# Power.net
KiCad netlist of a schematic drawn in Altium Designer
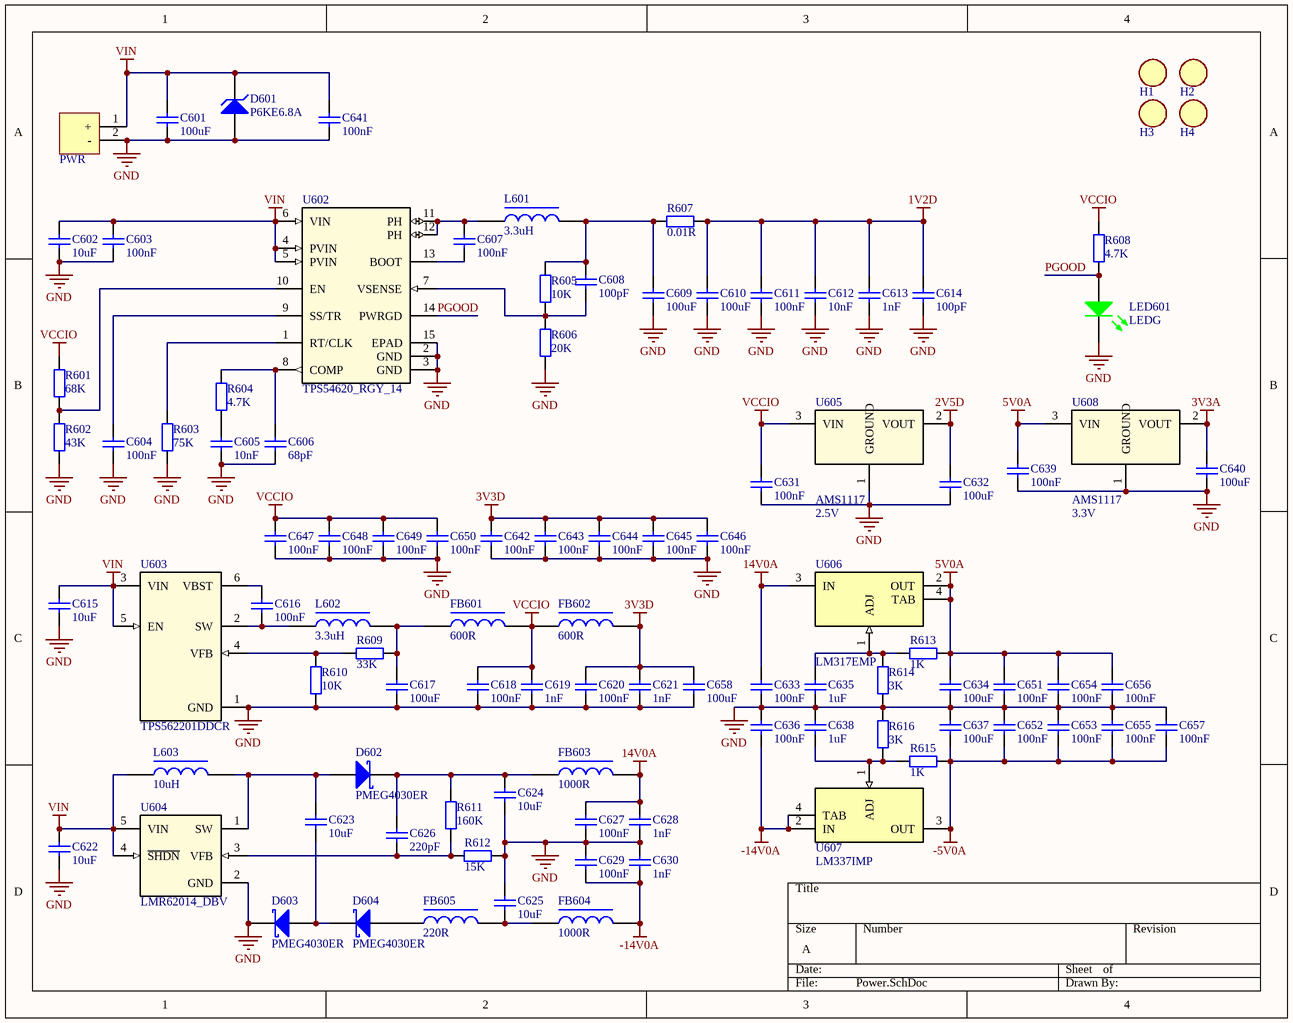
[diagram p0: Power.SchDoc]

(export (version "E")
  (design (tool "Eeschema 10.0.6"))
  (components
    (comp (ref "C601")
      (value "100uF")
      (footprint "1210C")
      (description "MLCC")
      (libsource (lib "Misc") (part "MLCC"))
    )
    (comp (ref "C602")
      (value "10uF")
      (footprint "1206C")
      (description "MLCC")
      (libsource (lib "Misc") (part "MLCC"))
    )
    (comp (ref "C603")
      (value "100nF")
      (footprint "0603C")
      (description "MLCC")
      (libsource (lib "Misc") (part "MLCC"))
    )
    (comp (ref "C604")
      (value "100nF")
      (footprint "0603C")
      (description "MLCC")
      (libsource (lib "Misc") (part "MLCC"))
    )
    (comp (ref "C605")
      (value "10nF")
      (footprint "0603C")
      (description "MLCC")
      (libsource (lib "Misc") (part "MLCC"))
    )
    (comp (ref "C606")
      (value "68pF")
      (footprint "0603C")
      (description "MLCC")
      (libsource (lib "Misc") (part "MLCC"))
    )
    (comp (ref "C607")
      (value "100nF")
      (footprint "0603C")
      (description "MLCC")
      (libsource (lib "Misc") (part "MLCC"))
    )
    (comp (ref "C608")
      (value "100pF")
      (footprint "0603C")
      (description "MLCC")
      (libsource (lib "Misc") (part "MLCC"))
    )
    (comp (ref "C609")
      (value "100uF")
      (footprint "1206C")
      (description "MLCC")
      (libsource (lib "Misc") (part "MLCC"))
    )
    (comp (ref "C610")
      (value "100uF")
      (footprint "1206C")
      (description "MLCC")
      (libsource (lib "Misc") (part "MLCC"))
    )
    (comp (ref "C611")
      (value "100nF")
      (footprint "0402C")
      (description "MLCC")
      (libsource (lib "Misc") (part "MLCC"))
    )
    (comp (ref "C612")
      (value "10nF")
      (footprint "0402C")
      (description "MLCC")
      (libsource (lib "Misc") (part "MLCC"))
    )
    (comp (ref "C613")
      (value "1nF")
      (footprint "0402C")
      (description "MLCC")
      (libsource (lib "Misc") (part "MLCC"))
    )
    (comp (ref "C614")
      (value "100pF")
      (footprint "0402C")
      (description "MLCC")
      (libsource (lib "Misc") (part "MLCC"))
    )
    (comp (ref "C615")
      (value "10uF")
      (footprint "1206C")
      (description "MLCC")
      (libsource (lib "Misc") (part "MLCC"))
    )
    (comp (ref "C616")
      (value "100nF")
      (footprint "0603C")
      (description "MLCC")
      (libsource (lib "Misc") (part "MLCC"))
    )
    (comp (ref "C617")
      (value "100uF")
      (footprint "1206C")
      (description "MLCC")
      (libsource (lib "Misc") (part "MLCC"))
    )
    (comp (ref "C618")
      (value "100nF")
      (footprint "0402C")
      (description "MLCC")
      (libsource (lib "Misc") (part "MLCC"))
    )
    (comp (ref "C619")
      (value "1nF")
      (footprint "0402C")
      (description "MLCC")
      (libsource (lib "Misc") (part "MLCC"))
    )
    (comp (ref "C620")
      (value "100nF")
      (footprint "0402C")
      (description "MLCC")
      (libsource (lib "Misc") (part "MLCC"))
    )
    (comp (ref "C621")
      (value "1nF")
      (footprint "0402C")
      (description "MLCC")
      (libsource (lib "Misc") (part "MLCC"))
    )
    (comp (ref "C622")
      (value "10uF")
      (footprint "1206C")
      (description "MLCC")
      (libsource (lib "Misc") (part "MLCC"))
    )
    (comp (ref "C623")
      (value "10uF")
      (footprint "1206C")
      (description "MLCC")
      (libsource (lib "Misc") (part "MLCC"))
    )
    (comp (ref "C624")
      (value "10uF")
      (footprint "1206C")
      (description "MLCC")
      (libsource (lib "Misc") (part "MLCC"))
    )
    (comp (ref "C625")
      (value "10uF")
      (footprint "1206C")
      (description "MLCC")
      (libsource (lib "Misc") (part "MLCC"))
    )
    (comp (ref "C626")
      (value "220pF")
      (footprint "0603C")
      (description "MLCC")
      (libsource (lib "Misc") (part "MLCC"))
    )
    (comp (ref "C627")
      (value "100nF")
      (footprint "0402C")
      (description "MLCC")
      (libsource (lib "Misc") (part "MLCC"))
    )
    (comp (ref "C628")
      (value "1nF")
      (footprint "0402C")
      (description "MLCC")
      (libsource (lib "Misc") (part "MLCC"))
    )
    (comp (ref "C629")
      (value "100nF")
      (footprint "0402C")
      (description "MLCC")
      (libsource (lib "Misc") (part "MLCC"))
    )
    (comp (ref "C630")
      (value "1nF")
      (footprint "0402C")
      (description "MLCC")
      (libsource (lib "Misc") (part "MLCC"))
    )
    (comp (ref "C631")
      (value "100nF")
      (footprint "0603C")
      (description "MLCC")
      (libsource (lib "Misc") (part "MLCC"))
    )
    (comp (ref "C632")
      (value "100uF")
      (footprint "1206C")
      (description "MLCC")
      (libsource (lib "Misc") (part "MLCC"))
    )
    (comp (ref "C633")
      (value "100nF")
      (footprint "0603C")
      (description "MLCC")
      (libsource (lib "Misc") (part "MLCC"))
    )
    (comp (ref "C634")
      (value "100uF")
      (footprint "1206C")
      (description "MLCC")
      (libsource (lib "Misc") (part "MLCC"))
    )
    (comp (ref "C635")
      (value "1uF")
      (footprint "0805C")
      (description "MLCC")
      (libsource (lib "Misc") (part "MLCC"))
    )
    (comp (ref "C636")
      (value "100nF")
      (footprint "0603C")
      (description "MLCC")
      (libsource (lib "Misc") (part "MLCC"))
    )
    (comp (ref "C637")
      (value "100uF")
      (footprint "1206C")
      (description "MLCC")
      (libsource (lib "Misc") (part "MLCC"))
    )
    (comp (ref "C638")
      (value "1uF")
      (footprint "0805C")
      (description "MLCC")
      (libsource (lib "Misc") (part "MLCC"))
    )
    (comp (ref "C639")
      (value "100nF")
      (footprint "0603C")
      (description "MLCC")
      (libsource (lib "Misc") (part "MLCC"))
    )
    (comp (ref "C640")
      (value "100uF")
      (footprint "1206C")
      (description "MLCC")
      (libsource (lib "Misc") (part "MLCC"))
    )
    (comp (ref "C641")
      (value "100nF")
      (footprint "0603C")
      (description "MLCC")
      (libsource (lib "Misc") (part "MLCC"))
    )
    (comp (ref "C642")
      (value "100nF")
      (footprint "0603C")
      (description "MLCC")
      (libsource (lib "Misc") (part "MLCC"))
    )
    (comp (ref "C643")
      (value "100nF")
      (footprint "0603C")
      (description "MLCC")
      (libsource (lib "Misc") (part "MLCC"))
    )
    (comp (ref "C644")
      (value "100nF")
      (footprint "0603C")
      (description "MLCC")
      (libsource (lib "Misc") (part "MLCC"))
    )
    (comp (ref "C645")
      (value "100nF")
      (footprint "0603C")
      (description "MLCC")
      (libsource (lib "Misc") (part "MLCC"))
    )
    (comp (ref "C646")
      (value "100nF")
      (footprint "0603C")
      (description "MLCC")
      (libsource (lib "Misc") (part "MLCC"))
    )
    (comp (ref "C647")
      (value "100nF")
      (footprint "0603C")
      (description "MLCC")
      (libsource (lib "Misc") (part "MLCC"))
    )
    (comp (ref "C648")
      (value "100nF")
      (footprint "0603C")
      (description "MLCC")
      (libsource (lib "Misc") (part "MLCC"))
    )
    (comp (ref "C649")
      (value "100nF")
      (footprint "0603C")
      (description "MLCC")
      (libsource (lib "Misc") (part "MLCC"))
    )
    (comp (ref "C650")
      (value "100nF")
      (footprint "0603C")
      (description "MLCC")
      (libsource (lib "Misc") (part "MLCC"))
    )
    (comp (ref "C651")
      (value "100nF")
      (footprint "0603C")
      (description "MLCC")
      (libsource (lib "Misc") (part "MLCC"))
    )
    (comp (ref "C652")
      (value "100nF")
      (footprint "0603C")
      (description "MLCC")
      (libsource (lib "Misc") (part "MLCC"))
    )
    (comp (ref "C653")
      (value "100nF")
      (footprint "0603C")
      (description "MLCC")
      (libsource (lib "Misc") (part "MLCC"))
    )
    (comp (ref "C654")
      (value "100nF")
      (footprint "0603C")
      (description "MLCC")
      (libsource (lib "Misc") (part "MLCC"))
    )
    (comp (ref "C655")
      (value "100nF")
      (footprint "0603C")
      (description "MLCC")
      (libsource (lib "Misc") (part "MLCC"))
    )
    (comp (ref "C656")
      (value "100nF")
      (footprint "0603C")
      (description "MLCC")
      (libsource (lib "Misc") (part "MLCC"))
    )
    (comp (ref "C657")
      (value "100nF")
      (footprint "0603C")
      (description "MLCC")
      (libsource (lib "Misc") (part "MLCC"))
    )
    (comp (ref "C658")
      (value "100uF")
      (footprint "1206C")
      (description "MLCC")
      (libsource (lib "Misc") (part "MLCC"))
    )
    (comp (ref "D601")
      (value "P6KE6.8A")
      (footprint "SMB")
      (description "600 Watt Peak Power Surmetict-40 Zener TransientVoltage Suppressors")
      (libsource (lib "Misc") (part "P6KE6.8A"))
    )
    (comp (ref "D602")
      (value "PMEG4030ER")
      (footprint "SOD123")
      (description "3 A low VF MEGA Schottky barrier rectifier")
      (libsource (lib "Misc") (part "PMEG4030ER"))
    )
    (comp (ref "D603")
      (value "PMEG4030ER")
      (footprint "SOD123")
      (description "3 A low VF MEGA Schottky barrier rectifier")
      (libsource (lib "Misc") (part "PMEG4030ER"))
    )
    (comp (ref "D604")
      (value "PMEG4030ER")
      (footprint "SOD123")
      (description "3 A low VF MEGA Schottky barrier rectifier")
      (libsource (lib "Misc") (part "PMEG4030ER"))
    )
    (comp (ref "FB601")
      (value "600R")
      (footprint "1206L")
      (description "FerriteBead")
      (libsource (lib "Misc") (part "FerriteBead"))
    )
    (comp (ref "FB602")
      (value "600R")
      (footprint "1206L")
      (description "FerriteBead")
      (libsource (lib "Misc") (part "FerriteBead"))
    )
    (comp (ref "FB603")
      (value "1000R")
      (footprint "0805L")
      (description "FerriteBead")
      (libsource (lib "Misc") (part "FerriteBead"))
    )
    (comp (ref "FB604")
      (value "1000R")
      (footprint "0805L")
      (description "FerriteBead")
      (libsource (lib "Misc") (part "FerriteBead"))
    )
    (comp (ref "FB605")
      (value "220R")
      (footprint "0805L")
      (description "FerriteBead")
      (libsource (lib "Misc") (part "FerriteBead"))
    )
    (comp (ref "H1")
      (value "MountHole")
      (footprint "MOUNTHOLE")
      (description "3mm mount hole")
      (libsource (lib "Misc") (part "MountHole"))
    )
    (comp (ref "H2")
      (value "MountHole")
      (footprint "MOUNTHOLE")
      (description "3mm mount hole")
      (libsource (lib "Misc") (part "MountHole"))
    )
    (comp (ref "H3")
      (value "MountHole")
      (footprint "MOUNTHOLE")
      (description "3mm mount hole")
      (libsource (lib "Misc") (part "MountHole"))
    )
    (comp (ref "H4")
      (value "MountHole")
      (footprint "MOUNTHOLE")
      (description "3mm mount hole")
      (libsource (lib "Misc") (part "MountHole"))
    )
    (comp (ref "L601")
      (value "3.3uH")
      (footprint "IND0630")
      (description "Power Inductor")
      (fields (field (name "Comment") "PowerInductor"))
      (libsource (lib "Misc") (part "PowerInductor"))
    )
    (comp (ref "L602")
      (value "3.3uH")
      (footprint "IND0420")
      (description "Power Inductor")
      (fields (field (name "Comment") "PowerInductor"))
      (libsource (lib "Misc") (part "PowerInductor"))
    )
    (comp (ref "L603")
      (value "10uH")
      (footprint "IND0420")
      (description "Power Inductor")
      (fields (field (name "Comment") "PowerInductor"))
      (libsource (lib "Misc") (part "PowerInductor"))
    )
    (comp (ref "LED601")
      (value "LEDG")
      (footprint "LED1206G")
      (description "GREEN LED")
      (libsource (lib "Misc") (part "LEDG"))
    )
    (comp (ref "PWR")
      (value "WPORT2_PWR")
      (footprint "VH3.96-POWER-2P")
      (description "2 pin power port")
      (libsource (lib "Ports3.96") (part "WPORT2_PWR"))
    )
    (comp (ref "R601")
      (value "68K")
      (footprint "0603R")
      (description "Resistor")
      (libsource (lib "Misc") (part "Resistor"))
    )
    (comp (ref "R602")
      (value "43K")
      (footprint "0603R")
      (description "Resistor")
      (libsource (lib "Misc") (part "Resistor"))
    )
    (comp (ref "R603")
      (value "75K")
      (footprint "0603R")
      (description "Resistor")
      (libsource (lib "Misc") (part "Resistor"))
    )
    (comp (ref "R604")
      (value "4.7K")
      (footprint "0603R")
      (description "Resistor")
      (libsource (lib "Misc") (part "Resistor"))
    )
    (comp (ref "R605")
      (value "10K")
      (footprint "0603R")
      (description "Resistor")
      (libsource (lib "Misc") (part "Resistor"))
    )
    (comp (ref "R606")
      (value "20K")
      (footprint "0603R")
      (description "Resistor")
      (libsource (lib "Misc") (part "Resistor"))
    )
    (comp (ref "R607")
      (value "0.01R")
      (footprint "1206R")
      (description "Resistor")
      (libsource (lib "") (part "Resistor_1"))
    )
    (comp (ref "R608")
      (value "4.7K")
      (footprint "0603R")
      (description "Resistor")
      (libsource (lib "Misc") (part "Resistor"))
    )
    (comp (ref "R609")
      (value "33K")
      (footprint "0603R")
      (description "Resistor")
      (libsource (lib "") (part "Resistor_1"))
    )
    (comp (ref "R610")
      (value "10K")
      (footprint "0603R")
      (description "Resistor")
      (libsource (lib "Misc") (part "Resistor"))
    )
    (comp (ref "R611")
      (value "160K")
      (footprint "0603R")
      (description "Resistor")
      (libsource (lib "Misc") (part "Resistor"))
    )
    (comp (ref "R612")
      (value "15K")
      (footprint "0603R")
      (description "Resistor")
      (libsource (lib "") (part "Resistor_1"))
    )
    (comp (ref "R613")
      (value "1K")
      (footprint "0603R")
      (description "Resistor")
      (libsource (lib "") (part "Resistor_1"))
    )
    (comp (ref "R614")
      (value "3K")
      (footprint "0603R")
      (description "Resistor")
      (libsource (lib "Misc") (part "Resistor"))
    )
    (comp (ref "R615")
      (value "1K")
      (footprint "0603R")
      (description "Resistor")
      (libsource (lib "") (part "Resistor_1"))
    )
    (comp (ref "R616")
      (value "3K")
      (footprint "0603R")
      (description "Resistor")
      (libsource (lib "Misc") (part "Resistor"))
    )
    (comp (ref "U602")
      (value "TPS54620_RGY_14")
      (footprint "RGY14_2P05X2P05")
      (fields
        (field (name "MANUFACTURER_PART_NUMBER") "tps54620_rgy_14")
        (field (name "GENERIC_PART_NUMBER") "TPS54620")
        (field (name "MANUFACTURER") "Texas Instruments")
      )
      (libsource (lib "SWReg") (part "TPS54620_RGY_14"))
    )
    (comp (ref "U603")
      (value "TPS562201DDCR")
      (footprint "DDC0006A_N")
      (description "4.5-V to 17-V Input, 2-A Synchronous Step-Down Voltage Regulator in 6-Pin SOT-23")
      (fields (field (name "MANUFACTURER") "Texas Instruments"))
      (libsource (lib "SWReg") (part "TPS562201DDCR"))
    )
    (comp (ref "U604")
      (value "LMR62014_DBV")
      (footprint "MF05A_N")
      (description "SIMPLE SWITCHER® 20Vout, 1.4A Step-Up Voltage Regulator in SOT-23")
      (fields (field (name "MANUFACTURER") "Texas Instruments"))
      (libsource (lib "SWReg") (part "LMR62014_DBV"))
    )
    (comp (ref "U605")
      (value "AMS1117")
      (footprint "DCY4")
      (description "800mA LOW DROPOUT VOLTAGE REGULATOR")
      (fields (field (name "ALTIUM_VALUE") "2.5V"))
      (libsource (lib "LDO") (part "AMS1117"))
    )
    (comp (ref "U606")
      (value "LM317EMP")
      (footprint "MP04A_N")
      (description "3-Terminal Adjustable Regulator, 4-pin SOT-223")
      (fields (field (name "MANUFACTURER") "National Semiconductor"))
      (libsource (lib "LDO") (part "LM317EMP"))
    )
    (comp (ref "U607")
      (value "LM337IMP")
      (footprint "MP04A_N")
      (description "3-Terminal Adjustable Negative Regulator, 4-pin SOT-223")
      (fields (field (name "MANUFACTURER") "National Semiconductor"))
      (libsource (lib "LDO") (part "LM337IMP"))
    )
    (comp (ref "U608")
      (value "AMS1117")
      (footprint "DCY4")
      (description "800mA LOW DROPOUT VOLTAGE REGULATOR")
      (fields (field (name "ALTIUM_VALUE") "3.3V"))
      (libsource (lib "LDO") (part "AMS1117"))
    )
  )
  (nets
    (net (code "1") (name "-5V0A") (class "Default")
      (node (ref "C637") (pin "1") (pinfunction "1_1") (pintype "passive"))
      (node (ref "C652") (pin "1") (pinfunction "1_1") (pintype "passive"))
      (node (ref "C653") (pin "1") (pinfunction "1_1") (pintype "passive"))
      (node (ref "C655") (pin "1") (pinfunction "1_1") (pintype "passive"))
      (node (ref "C657") (pin "1") (pinfunction "1_1") (pintype "passive"))
      (node (ref "R615") (pin "2") (pinfunction "2_2") (pintype "passive"))
      (node (ref "U607") (pin "3") (pinfunction "OUT_3") (pintype "power_in"))
    )
    (net (code "2") (name "-14V0A") (class "Default")
      (node (ref "C629") (pin "1") (pinfunction "1_1") (pintype "passive"))
      (node (ref "C630") (pin "1") (pinfunction "1_1") (pintype "passive"))
      (node (ref "C636") (pin "1") (pinfunction "1_1") (pintype "passive"))
      (node (ref "FB604") (pin "2") (pinfunction "2_2") (pintype "passive"))
      (node (ref "U607") (pin "2") (pinfunction "IN_2") (pintype "power_in"))
      (node (ref "U607") (pin "4") (pinfunction "TAB_4") (pintype "power_in"))
    )
    (net (code "3") (name "/PGOOD") (class "Default")
      (node (ref "LED601") (pin "1") (pinfunction "A_1") (pintype "passive"))
      (node (ref "R608") (pin "1") (pinfunction "1_1") (pintype "passive"))
      (node (ref "U602") (pin "14") (pinfunction "PWRGD_14") (pintype "power_in"))
    )
    (net (code "4") (name "1V2D") (class "Default")
      (node (ref "C610") (pin "2") (pinfunction "2_2") (pintype "passive"))
      (node (ref "C611") (pin "2") (pinfunction "2_2") (pintype "passive"))
      (node (ref "C612") (pin "2") (pinfunction "2_2") (pintype "passive"))
      (node (ref "C613") (pin "2") (pinfunction "2_2") (pintype "passive"))
      (node (ref "C614") (pin "2") (pinfunction "2_2") (pintype "passive"))
      (node (ref "R607") (pin "2") (pinfunction "2_2") (pintype "passive"))
    )
    (net (code "5") (name "2V5D") (class "Default")
      (node (ref "C632") (pin "2") (pinfunction "2_2") (pintype "passive"))
      (node (ref "U605") (pin "2") (pinfunction "VOUT_2") (pintype "power_in"))
    )
    (net (code "6") (name "3V3A") (class "Default")
      (node (ref "C640") (pin "2") (pinfunction "2_2") (pintype "passive"))
      (node (ref "U608") (pin "2") (pinfunction "VOUT_2") (pintype "power_in"))
    )
    (net (code "7") (name "3V3D") (class "Default")
      (node (ref "C620") (pin "2") (pinfunction "2_2") (pintype "passive"))
      (node (ref "C621") (pin "2") (pinfunction "2_2") (pintype "passive"))
      (node (ref "C642") (pin "2") (pinfunction "2_2") (pintype "passive"))
      (node (ref "C643") (pin "2") (pinfunction "2_2") (pintype "passive"))
      (node (ref "C644") (pin "2") (pinfunction "2_2") (pintype "passive"))
      (node (ref "C645") (pin "2") (pinfunction "2_2") (pintype "passive"))
      (node (ref "C646") (pin "2") (pinfunction "2_2") (pintype "passive"))
      (node (ref "C658") (pin "2") (pinfunction "2_2") (pintype "passive"))
      (node (ref "FB602") (pin "2") (pinfunction "2_2") (pintype "passive"))
    )
    (net (code "8") (name "5V0A") (class "Default")
      (node (ref "C634") (pin "2") (pinfunction "2_2") (pintype "passive"))
      (node (ref "C639") (pin "2") (pinfunction "2_2") (pintype "passive"))
      (node (ref "C651") (pin "2") (pinfunction "2_2") (pintype "passive"))
      (node (ref "C654") (pin "2") (pinfunction "2_2") (pintype "passive"))
      (node (ref "C656") (pin "2") (pinfunction "2_2") (pintype "passive"))
      (node (ref "R613") (pin "2") (pinfunction "2_2") (pintype "passive"))
      (node (ref "U606") (pin "2") (pinfunction "OUT_2") (pintype "power_in"))
      (node (ref "U606") (pin "4") (pinfunction "TAB_4") (pintype "power_in"))
      (node (ref "U608") (pin "3") (pinfunction "VIN_3") (pintype "power_in"))
    )
    (net (code "9") (name "14V0A") (class "Default")
      (node (ref "C627") (pin "2") (pinfunction "2_2") (pintype "passive"))
      (node (ref "C628") (pin "2") (pinfunction "2_2") (pintype "passive"))
      (node (ref "C633") (pin "2") (pinfunction "2_2") (pintype "passive"))
      (node (ref "FB603") (pin "2") (pinfunction "2_2") (pintype "passive"))
      (node (ref "U606") (pin "3") (pinfunction "IN_3") (pintype "power_in"))
    )
    (net (code "10") (name "GND") (class "Default")
      (node (ref "C601") (pin "1") (pinfunction "1_1") (pintype "passive"))
      (node (ref "C602") (pin "1") (pinfunction "1_1") (pintype "passive"))
      (node (ref "C603") (pin "1") (pinfunction "1_1") (pintype "passive"))
      (node (ref "C604") (pin "1") (pinfunction "1_1") (pintype "passive"))
      (node (ref "C605") (pin "1") (pinfunction "1_1") (pintype "passive"))
      (node (ref "C606") (pin "1") (pinfunction "1_1") (pintype "passive"))
      (node (ref "C609") (pin "1") (pinfunction "1_1") (pintype "passive"))
      (node (ref "C610") (pin "1") (pinfunction "1_1") (pintype "passive"))
      (node (ref "C611") (pin "1") (pinfunction "1_1") (pintype "passive"))
      (node (ref "C612") (pin "1") (pinfunction "1_1") (pintype "passive"))
      (node (ref "C613") (pin "1") (pinfunction "1_1") (pintype "passive"))
      (node (ref "C614") (pin "1") (pinfunction "1_1") (pintype "passive"))
      (node (ref "C615") (pin "1") (pinfunction "1_1") (pintype "passive"))
      (node (ref "C617") (pin "1") (pinfunction "1_1") (pintype "passive"))
      (node (ref "C618") (pin "1") (pinfunction "1_1") (pintype "passive"))
      (node (ref "C619") (pin "1") (pinfunction "1_1") (pintype "passive"))
      (node (ref "C620") (pin "1") (pinfunction "1_1") (pintype "passive"))
      (node (ref "C621") (pin "1") (pinfunction "1_1") (pintype "passive"))
      (node (ref "C622") (pin "1") (pinfunction "1_1") (pintype "passive"))
      (node (ref "C624") (pin "1") (pinfunction "1_1") (pintype "passive"))
      (node (ref "C625") (pin "2") (pinfunction "2_2") (pintype "passive"))
      (node (ref "C627") (pin "1") (pinfunction "1_1") (pintype "passive"))
      (node (ref "C628") (pin "1") (pinfunction "1_1") (pintype "passive"))
      (node (ref "C629") (pin "2") (pinfunction "2_2") (pintype "passive"))
      (node (ref "C630") (pin "2") (pinfunction "2_2") (pintype "passive"))
      (node (ref "C631") (pin "1") (pinfunction "1_1") (pintype "passive"))
      (node (ref "C632") (pin "1") (pinfunction "1_1") (pintype "passive"))
      (node (ref "C633") (pin "1") (pinfunction "1_1") (pintype "passive"))
      (node (ref "C634") (pin "1") (pinfunction "1_1") (pintype "passive"))
      (node (ref "C635") (pin "1") (pinfunction "1_1") (pintype "passive"))
      (node (ref "C636") (pin "2") (pinfunction "2_2") (pintype "passive"))
      (node (ref "C637") (pin "2") (pinfunction "2_2") (pintype "passive"))
      (node (ref "C638") (pin "2") (pinfunction "2_2") (pintype "passive"))
      (node (ref "C639") (pin "1") (pinfunction "1_1") (pintype "passive"))
      (node (ref "C640") (pin "1") (pinfunction "1_1") (pintype "passive"))
      (node (ref "C641") (pin "1") (pinfunction "1_1") (pintype "passive"))
      (node (ref "C642") (pin "1") (pinfunction "1_1") (pintype "passive"))
      (node (ref "C643") (pin "1") (pinfunction "1_1") (pintype "passive"))
      (node (ref "C644") (pin "1") (pinfunction "1_1") (pintype "passive"))
      (node (ref "C645") (pin "1") (pinfunction "1_1") (pintype "passive"))
      (node (ref "C646") (pin "1") (pinfunction "1_1") (pintype "passive"))
      (node (ref "C647") (pin "1") (pinfunction "1_1") (pintype "passive"))
      (node (ref "C648") (pin "1") (pinfunction "1_1") (pintype "passive"))
      (node (ref "C649") (pin "1") (pinfunction "1_1") (pintype "passive"))
      (node (ref "C650") (pin "1") (pinfunction "1_1") (pintype "passive"))
      (node (ref "C651") (pin "1") (pinfunction "1_1") (pintype "passive"))
      (node (ref "C652") (pin "2") (pinfunction "2_2") (pintype "passive"))
      (node (ref "C653") (pin "2") (pinfunction "2_2") (pintype "passive"))
      (node (ref "C654") (pin "1") (pinfunction "1_1") (pintype "passive"))
      (node (ref "C655") (pin "2") (pinfunction "2_2") (pintype "passive"))
      (node (ref "C656") (pin "1") (pinfunction "1_1") (pintype "passive"))
      (node (ref "C657") (pin "2") (pinfunction "2_2") (pintype "passive"))
      (node (ref "C658") (pin "1") (pinfunction "1_1") (pintype "passive"))
      (node (ref "D601") (pin "1") (pinfunction "A_1") (pintype "passive"))
      (node (ref "D603") (pin "2") (pinfunction "K_2") (pintype "passive"))
      (node (ref "LED601") (pin "2") (pinfunction "K_2") (pintype "passive"))
      (node (ref "PWR") (pin "2") (pinfunction "-_2") (pintype "passive"))
      (node (ref "R602") (pin "1") (pinfunction "1_1") (pintype "passive"))
      (node (ref "R603") (pin "1") (pinfunction "1_1") (pintype "passive"))
      (node (ref "R606") (pin "1") (pinfunction "1_1") (pintype "passive"))
      (node (ref "R610") (pin "1") (pinfunction "1_1") (pintype "passive"))
      (node (ref "R612") (pin "2") (pinfunction "2_2") (pintype "passive"))
      (node (ref "R614") (pin "1") (pinfunction "1_1") (pintype "passive"))
      (node (ref "R616") (pin "2") (pinfunction "2_2") (pintype "passive"))
      (node (ref "U602") (pin "15") (pinfunction "EPAD_15") (pintype "passive"))
      (node (ref "U602") (pin "2") (pinfunction "GND_2") (pintype "power_in"))
      (node (ref "U602") (pin "3") (pinfunction "GND_3") (pintype "power_in"))
      (node (ref "U603") (pin "1") (pinfunction "GND_1") (pintype "power_in"))
      (node (ref "U604") (pin "2") (pinfunction "GND_2") (pintype "power_in"))
      (node (ref "U605") (pin "1") (pinfunction "GROUND_1") (pintype "power_in"))
      (node (ref "U608") (pin "1") (pinfunction "GROUND_1") (pintype "power_in"))
    )
    (net (code "11") (name "Net-(C605-Pad2)") (class "Default")
      (node (ref "C605") (pin "2") (pinfunction "2_2") (pintype "passive"))
      (node (ref "R604") (pin "1") (pinfunction "1_1") (pintype "passive"))
    )
    (net (code "12") (name "Net-(C607-Pad2)") (class "Default")
      (node (ref "C607") (pin "2") (pinfunction "2_2") (pintype "passive"))
      (node (ref "L601") (pin "1") (pinfunction "1_1") (pintype "passive"))
      (node (ref "U602") (pin "11") (pinfunction "PH_11") (pintype "bidirectional"))
      (node (ref "U602") (pin "12") (pinfunction "PH_12") (pintype "bidirectional"))
    )
    (net (code "13") (name "Net-(C608-Pad2)") (class "Default")
      (node (ref "C608") (pin "2") (pinfunction "2_2") (pintype "passive"))
      (node (ref "C609") (pin "2") (pinfunction "2_2") (pintype "passive"))
      (node (ref "L601") (pin "2") (pinfunction "2_2") (pintype "passive"))
      (node (ref "R605") (pin "2") (pinfunction "2_2") (pintype "passive"))
      (node (ref "R607") (pin "1") (pinfunction "1_1") (pintype "passive"))
    )
    (net (code "14") (name "Net-(C617-Pad2)") (class "Default")
      (node (ref "C617") (pin "2") (pinfunction "2_2") (pintype "passive"))
      (node (ref "FB601") (pin "1") (pinfunction "1_1") (pintype "passive"))
      (node (ref "L602") (pin "2") (pinfunction "2_2") (pintype "passive"))
      (node (ref "R609") (pin "2") (pinfunction "2_2") (pintype "passive"))
    )
    (net (code "15") (name "Net-(C625-Pad1)") (class "Default")
      (node (ref "C625") (pin "1") (pinfunction "1_1") (pintype "passive"))
      (node (ref "FB604") (pin "1") (pinfunction "1_1") (pintype "passive"))
      (node (ref "FB605") (pin "2") (pinfunction "2_2") (pintype "passive"))
    )
    (net (code "16") (name "Net-(D602-A)") (class "Default")
      (node (ref "C623") (pin "2") (pinfunction "2_2") (pintype "passive"))
      (node (ref "D602") (pin "1") (pinfunction "A_1") (pintype "passive"))
      (node (ref "L603") (pin "2") (pinfunction "2_2") (pintype "passive"))
      (node (ref "U604") (pin "1") (pinfunction "SW_1") (pintype "power_in"))
    )
    (net (code "17") (name "Net-(D602-K)") (class "Default")
      (node (ref "C624") (pin "2") (pinfunction "2_2") (pintype "passive"))
      (node (ref "C626") (pin "2") (pinfunction "2_2") (pintype "passive"))
      (node (ref "D602") (pin "2") (pinfunction "K_2") (pintype "passive"))
      (node (ref "FB603") (pin "1") (pinfunction "1_1") (pintype "passive"))
      (node (ref "R611") (pin "2") (pinfunction "2_2") (pintype "passive"))
    )
    (net (code "18") (name "Net-(D603-A)") (class "Default")
      (node (ref "C623") (pin "1") (pinfunction "1_1") (pintype "passive"))
      (node (ref "D603") (pin "1") (pinfunction "A_1") (pintype "passive"))
      (node (ref "D604") (pin "2") (pinfunction "K_2") (pintype "passive"))
    )
    (net (code "19") (name "Net-(D604-A)") (class "Default")
      (node (ref "D604") (pin "1") (pinfunction "A_1") (pintype "passive"))
      (node (ref "FB605") (pin "1") (pinfunction "1_1") (pintype "passive"))
    )
    (net (code "20") (name "Net-(U602-BOOT)") (class "Default")
      (node (ref "C607") (pin "1") (pinfunction "1_1") (pintype "passive"))
      (node (ref "U602") (pin "13") (pinfunction "BOOT_13") (pintype "passive"))
    )
    (net (code "21") (name "Net-(U602-COMP)") (class "Default")
      (node (ref "C606") (pin "2") (pinfunction "2_2") (pintype "passive"))
      (node (ref "R604") (pin "2") (pinfunction "2_2") (pintype "passive"))
      (node (ref "U602") (pin "8") (pinfunction "COMP_8") (pintype "output"))
    )
    (net (code "22") (name "Net-(U602-EN)") (class "Default")
      (node (ref "R601") (pin "1") (pinfunction "1_1") (pintype "passive"))
      (node (ref "R602") (pin "2") (pinfunction "2_2") (pintype "passive"))
      (node (ref "U602") (pin "10") (pinfunction "EN_10") (pintype "passive"))
    )
    (net (code "23") (name "Net-(U602-RT{slash}CLK)") (class "Default")
      (node (ref "R603") (pin "2") (pinfunction "2_2") (pintype "passive"))
      (node (ref "U602") (pin "1") (pinfunction "RT/CLK_1") (pintype "passive"))
    )
    (net (code "24") (name "Net-(U602-SS{slash}TR)") (class "Default")
      (node (ref "C604") (pin "2") (pinfunction "2_2") (pintype "passive"))
      (node (ref "U602") (pin "9") (pinfunction "SS/TR_9") (pintype "passive"))
    )
    (net (code "25") (name "Net-(U602-VSENSE)") (class "Default")
      (node (ref "C608") (pin "1") (pinfunction "1_1") (pintype "passive"))
      (node (ref "R605") (pin "1") (pinfunction "1_1") (pintype "passive"))
      (node (ref "R606") (pin "2") (pinfunction "2_2") (pintype "passive"))
      (node (ref "U602") (pin "7") (pinfunction "VSENSE_7") (pintype "input"))
    )
    (net (code "26") (name "Net-(U603-SW)") (class "Default")
      (node (ref "C616") (pin "1") (pinfunction "1_1") (pintype "passive"))
      (node (ref "L602") (pin "1") (pinfunction "1_1") (pintype "passive"))
      (node (ref "U603") (pin "2") (pinfunction "SW_2") (pintype "power_in"))
    )
    (net (code "27") (name "Net-(U603-VBST)") (class "Default")
      (node (ref "C616") (pin "2") (pinfunction "2_2") (pintype "passive"))
      (node (ref "U603") (pin "6") (pinfunction "VBST_6") (pintype "power_in"))
    )
    (net (code "28") (name "Net-(U603-VFB)") (class "Default")
      (node (ref "R609") (pin "1") (pinfunction "1_1") (pintype "passive"))
      (node (ref "R610") (pin "2") (pinfunction "2_2") (pintype "passive"))
      (node (ref "U603") (pin "4") (pinfunction "VFB_4") (pintype "input"))
    )
    (net (code "29") (name "Net-(U604-VFB)") (class "Default")
      (node (ref "C626") (pin "1") (pinfunction "1_1") (pintype "passive"))
      (node (ref "R611") (pin "1") (pinfunction "1_1") (pintype "passive"))
      (node (ref "R612") (pin "1") (pinfunction "1_1") (pintype "passive"))
      (node (ref "U604") (pin "3") (pinfunction "VFB_3") (pintype "input"))
    )
    (net (code "30") (name "Net-(U606-ADJ)") (class "Default")
      (node (ref "C635") (pin "2") (pinfunction "2_2") (pintype "passive"))
      (node (ref "R613") (pin "1") (pinfunction "1_1") (pintype "passive"))
      (node (ref "R614") (pin "2") (pinfunction "2_2") (pintype "passive"))
      (node (ref "U606") (pin "1") (pinfunction "ADJ_1") (pintype "input"))
    )
    (net (code "31") (name "Net-(U607-ADJ)") (class "Default")
      (node (ref "C638") (pin "1") (pinfunction "1_1") (pintype "passive"))
      (node (ref "R615") (pin "1") (pinfunction "1_1") (pintype "passive"))
      (node (ref "R616") (pin "1") (pinfunction "1_1") (pintype "passive"))
      (node (ref "U607") (pin "1") (pinfunction "ADJ_1") (pintype "input"))
    )
    (net (code "32") (name "VCCIO") (class "Default")
      (node (ref "C618") (pin "2") (pinfunction "2_2") (pintype "passive"))
      (node (ref "C619") (pin "2") (pinfunction "2_2") (pintype "passive"))
      (node (ref "C631") (pin "2") (pinfunction "2_2") (pintype "passive"))
      (node (ref "C647") (pin "2") (pinfunction "2_2") (pintype "passive"))
      (node (ref "C648") (pin "2") (pinfunction "2_2") (pintype "passive"))
      (node (ref "C649") (pin "2") (pinfunction "2_2") (pintype "passive"))
      (node (ref "C650") (pin "2") (pinfunction "2_2") (pintype "passive"))
      (node (ref "FB601") (pin "2") (pinfunction "2_2") (pintype "passive"))
      (node (ref "FB602") (pin "1") (pinfunction "1_1") (pintype "passive"))
      (node (ref "R601") (pin "2") (pinfunction "2_2") (pintype "passive"))
      (node (ref "R608") (pin "2") (pinfunction "2_2") (pintype "passive"))
      (node (ref "U605") (pin "3") (pinfunction "VIN_3") (pintype "power_in"))
    )
    (net (code "33") (name "VIN") (class "Default")
      (node (ref "C601") (pin "2") (pinfunction "2_2") (pintype "passive"))
      (node (ref "C602") (pin "2") (pinfunction "2_2") (pintype "passive"))
      (node (ref "C603") (pin "2") (pinfunction "2_2") (pintype "passive"))
      (node (ref "C615") (pin "2") (pinfunction "2_2") (pintype "passive"))
      (node (ref "C622") (pin "2") (pinfunction "2_2") (pintype "passive"))
      (node (ref "C641") (pin "2") (pinfunction "2_2") (pintype "passive"))
      (node (ref "D601") (pin "2") (pinfunction "K_2") (pintype "passive"))
      (node (ref "L603") (pin "1") (pinfunction "1_1") (pintype "passive"))
      (node (ref "PWR") (pin "1") (pinfunction "+_1") (pintype "passive"))
      (node (ref "U602") (pin "4") (pinfunction "PVIN_4") (pintype "input"))
      (node (ref "U602") (pin "5") (pinfunction "PVIN_5") (pintype "input"))
      (node (ref "U602") (pin "6") (pinfunction "VIN_6") (pintype "input"))
      (node (ref "U603") (pin "3") (pinfunction "VIN_3") (pintype "power_in"))
      (node (ref "U603") (pin "5") (pinfunction "EN_5") (pintype "input"))
      (node (ref "U604") (pin "4") (pinfunction "~{SHDN}_4") (pintype "input"))
      (node (ref "U604") (pin "5") (pinfunction "VIN_5") (pintype "power_in"))
    )
  )
)
